# Kinetic_reva.net
KiCad netlist of a schematic drawn in EAGLE
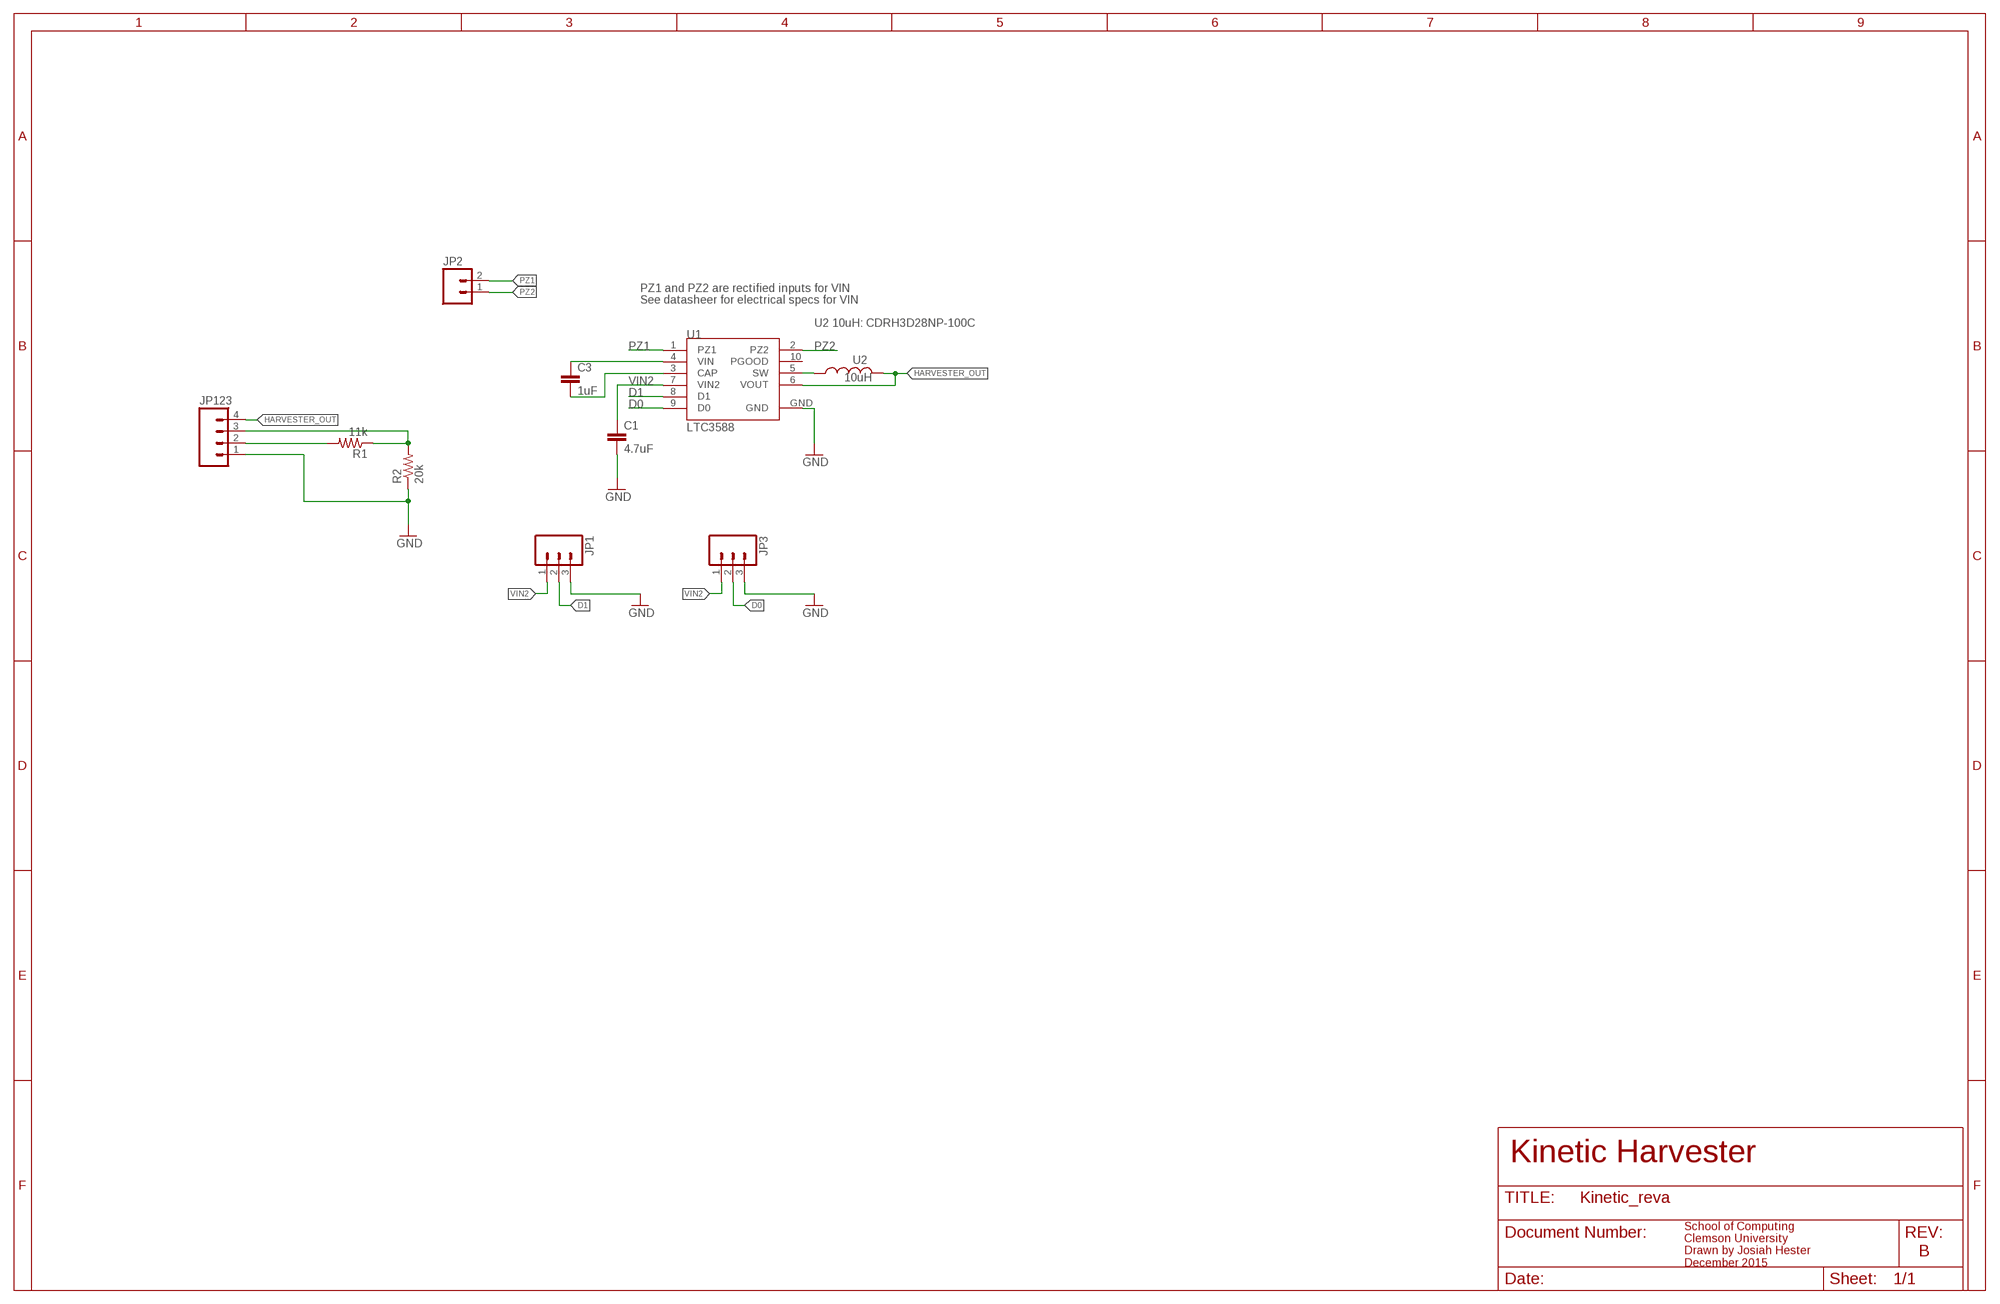
[diagram p0: schematic, sheet 1]

(export (version "E")
  (design (tool "Eeschema 10.0.6"))
  (components
    (comp (ref "C1")
      (value "4.7uF")
      (footprint "eagle-import:0402-CAP")
      (fields (field (name "MPN") "C1005X5R1A475M050BC"))
      (libsource (lib "eagle-import") (part "CAP0402-CAP"))
    )
    (comp (ref "C3")
      (value "1uF")
      (footprint "eagle-import:0402-CAP")
      (fields (field (name "MPN") "0402ZD105KAT2A"))
      (libsource (lib "eagle-import") (part "CAP0402-CAP"))
    )
    (comp (ref "JP1")
      (value "M03")
      (footprint "eagle-import:1X03-1.27MM")
      (fields (field (name "MPN") "GRPB031VWVN-RC "))
      (libsource (lib "eagle-import") (part "M03"))
    )
    (comp (ref "JP2")
      (value "M02LOCK")
      (footprint "eagle-import:1X02_LOCK")
      (libsource (lib "eagle-import") (part "M02LOCK"))
    )
    (comp (ref "JP3")
      (value "M03")
      (footprint "eagle-import:1X03-1.27MM")
      (fields (field (name "MPN") "GRPB031VWVN-RC "))
      (libsource (lib "eagle-import") (part "M03"))
    )
    (comp (ref "JP123")
      (value "M041.27MM")
      (footprint "eagle-import:1X04-1.27MM")
      (fields (field (name "MPN") "GRPB041VWVN-RC "))
      (libsource (lib "eagle-import") (part "M041.27MM"))
    )
    (comp (ref "R1")
      (value "11k")
      (footprint "eagle-import:0603")
      (fields (field (name "MPN") "RC0603JR-0711KL"))
      (libsource (lib "eagle-import") (part "R-EU0603"))
    )
    (comp (ref "R2")
      (value "20k")
      (footprint "eagle-import:0603")
      (fields (field (name "MPN") "CRCW060320K0FKEA"))
      (libsource (lib "eagle-import") (part "R-EU0603"))
    )
    (comp (ref "U1")
      (value "LTC3588")
      (footprint "eagle-import:MSOP-10-GNDPAD")
      (fields (field (name "MPN") "LTC3588EMSE-1#PBF "))
      (libsource (lib "eagle-import") (part "LTC3588_"))
    )
    (comp (ref "U2")
      (value "10uH")
      (footprint "eagle-import:CDRH3D28")
      (fields (field (name "MPN") "CDRH3D16NP-100NC "))
      (libsource (lib "eagle-import") (part "INDUCTOR-"))
    )
  )
  (nets
    (net (code "1") (name "D0") (class "Default")
      (node (ref "JP3") (pin "2") (pinfunction "2_2") (pintype "passive"))
      (node (ref "U1") (pin "9") (pinfunction "D0_9") (pintype "bidirectional"))
    )
    (net (code "2") (name "D1") (class "Default")
      (node (ref "JP1") (pin "2") (pinfunction "2_2") (pintype "passive"))
      (node (ref "U1") (pin "8") (pinfunction "D1_8") (pintype "bidirectional"))
    )
    (net (code "3") (name "GND") (class "Default")
      (node (ref "C1") (pin "2") (pinfunction "2_2") (pintype "passive"))
      (node (ref "JP1") (pin "3") (pinfunction "3_3") (pintype "passive"))
      (node (ref "JP123") (pin "1") (pinfunction "1_1") (pintype "passive"))
      (node (ref "JP3") (pin "3") (pinfunction "3_3") (pintype "passive"))
      (node (ref "R2") (pin "1") (pinfunction "1_1") (pintype "passive"))
      (node (ref "U1") (pin "GND") (pinfunction "GND_GND") (pintype "bidirectional"))
    )
    (net (code "4") (name "HARVESTER_OUT") (class "Default")
      (node (ref "JP123") (pin "4") (pinfunction "4_4") (pintype "passive"))
      (node (ref "U1") (pin "6") (pinfunction "VOUT_6") (pintype "bidirectional"))
      (node (ref "U2") (pin "2") (pinfunction "2_2") (pintype "passive"))
    )
    (net (code "5") (name "Net-(JP123-Pad2)") (class "Default")
      (node (ref "JP123") (pin "2") (pinfunction "2_2") (pintype "passive"))
      (node (ref "R1") (pin "2") (pinfunction "2_2") (pintype "passive"))
    )
    (net (code "6") (name "Net-(JP123-Pad3)") (class "Default")
      (node (ref "JP123") (pin "3") (pinfunction "3_3") (pintype "passive"))
      (node (ref "R1") (pin "1") (pinfunction "1_1") (pintype "passive"))
      (node (ref "R2") (pin "2") (pinfunction "2_2") (pintype "passive"))
    )
    (net (code "7") (name "Net-(U1-CAP)") (class "Default")
      (node (ref "C3") (pin "2") (pinfunction "2_2") (pintype "passive"))
      (node (ref "U1") (pin "3") (pinfunction "CAP_3") (pintype "bidirectional"))
    )
    (net (code "8") (name "Net-(U1-SW)") (class "Default")
      (node (ref "U1") (pin "5") (pinfunction "SW_5") (pintype "bidirectional"))
      (node (ref "U2") (pin "1") (pinfunction "1_1") (pintype "passive"))
    )
    (net (code "9") (name "Net-(U1-VIN)") (class "Default")
      (node (ref "C3") (pin "1") (pinfunction "1_1") (pintype "passive"))
      (node (ref "U1") (pin "4") (pinfunction "VIN_4") (pintype "bidirectional"))
    )
    (net (code "10") (name "PZ1") (class "Default")
      (node (ref "JP2") (pin "2") (pinfunction "2_2") (pintype "passive"))
      (node (ref "U1") (pin "1") (pinfunction "PZ1_1") (pintype "bidirectional"))
    )
    (net (code "11") (name "PZ2") (class "Default")
      (node (ref "JP2") (pin "1") (pinfunction "1_1") (pintype "passive"))
      (node (ref "U1") (pin "2") (pinfunction "PZ2_2") (pintype "bidirectional"))
    )
    (net (code "12") (name "VIN2") (class "Default")
      (node (ref "C1") (pin "1") (pinfunction "1_1") (pintype "passive"))
      (node (ref "JP1") (pin "1") (pinfunction "1_1") (pintype "passive"))
      (node (ref "JP3") (pin "1") (pinfunction "1_1") (pintype "passive"))
      (node (ref "U1") (pin "7") (pinfunction "VIN2_7") (pintype "bidirectional"))
    )
    (net (code "13") (name "unconnected-(U1-PGOOD-Pad10)") (class "Default")
      (node (ref "U1") (pin "10") (pinfunction "PGOOD_10") (pintype "bidirectional"))
    )
  )
)
